# DAC.net
KiCad netlist of a schematic drawn in Altium Designer
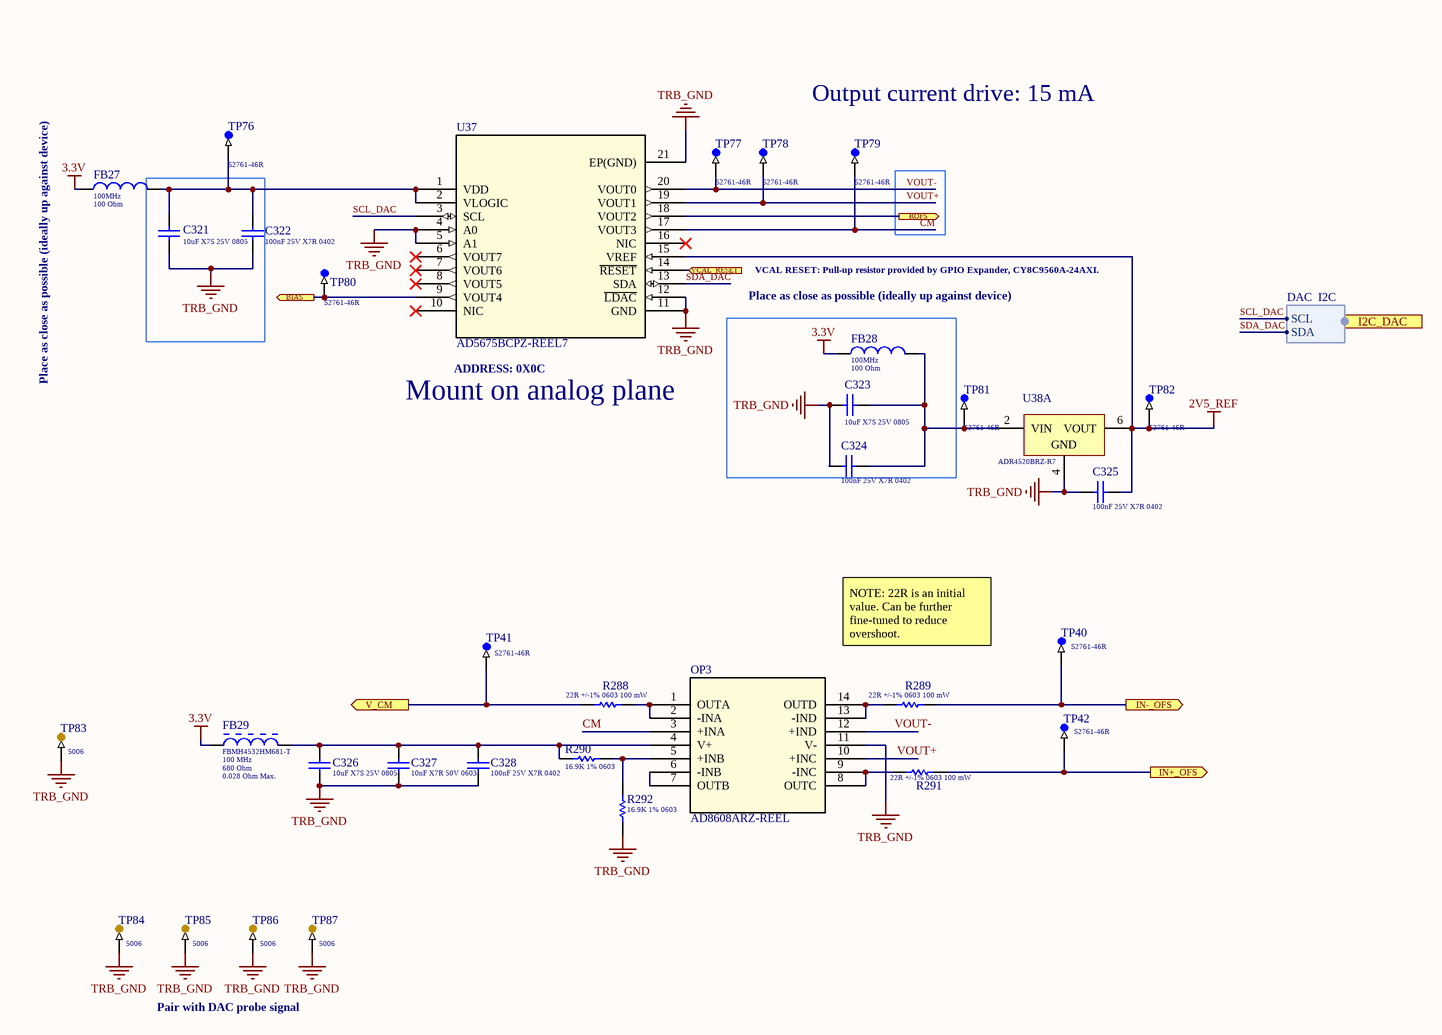
[diagram p0: DAC.SchDoc]

(export (version "E")
  (design (tool "Eeschema 10.0.6"))
  (components
    (comp (ref "C321")
      (value "Cap_Murata_ GRM21BC71E106ME11L_10uF")
      (footprint "Cap_Murata_ GRM21BC71E106ME11L_10uF")
      (description "CAP CER 10uF 25V X7R 0805")
      (fields (field (name "CAPACITANCE") "10uF X7S 25V 0805"))
      (libsource (lib "Cap_Murata_ GRM21BC71E106ME11L_10uF") (part "Cap_Murata_ GRM21BC71E106ME11L_10uF"))
    )
    (comp (ref "C322")
      (value "Cap_Taiyo_Yuden_TMK105B7104KV-FR_100nF")
      (footprint "Cap_Taiyo_Yuden_TMK105B7104KV-FR_100nF")
      (description "CAP CER 100nF 25V X7R 0402")
      (fields (field (name "CAPACITANCE") "100nF 25V X7R 0402"))
      (libsource (lib "Cap_Taiyo_Yuden_TMK105B7104KV-FR_100nF") (part "Cap_Taiyo_Yuden_TMK105B7104KV-FR_100nF"))
    )
    (comp (ref "C323")
      (value "Cap_Murata_ GRM21BC71E106ME11L_10uF")
      (footprint "Cap_Murata_ GRM21BC71E106ME11L_10uF")
      (description "CAP CER 10uF 25V X7R 0805")
      (fields (field (name "CAPACITANCE") "10uF X7S 25V 0805"))
      (libsource (lib "Cap_Murata_ GRM21BC71E106ME11L_10uF") (part "Cap_Murata_ GRM21BC71E106ME11L_10uF"))
    )
    (comp (ref "C324")
      (value "Cap_Taiyo_Yuden_TMK105B7104KV-FR_100nF")
      (footprint "Cap_Taiyo_Yuden_TMK105B7104KV-FR_100nF")
      (description "CAP CER 100nF 25V X7R 0402")
      (fields (field (name "CAPACITANCE") "100nF 25V X7R 0402"))
      (libsource (lib "Cap_Taiyo_Yuden_TMK105B7104KV-FR_100nF") (part "Cap_Taiyo_Yuden_TMK105B7104KV-FR_100nF"))
    )
    (comp (ref "C325")
      (value "Cap_Taiyo_Yuden_TMK105B7104KV-FR_100nF")
      (footprint "Cap_Taiyo_Yuden_TMK105B7104KV-FR_100nF")
      (description "CAP CER 100nF 25V X7R 0402")
      (fields (field (name "CAPACITANCE") "100nF 25V X7R 0402"))
      (libsource (lib "Cap_Taiyo_Yuden_TMK105B7104KV-FR_100nF") (part "Cap_Taiyo_Yuden_TMK105B7104KV-FR_100nF"))
    )
    (comp (ref "C326")
      (value "Cap_Murata_ GRM21BC71E106ME11L_10uF")
      (footprint "Cap_Murata_ GRM21BC71E106ME11L_10uF")
      (description "CAP CER 10uF 25V X7R 0805")
      (fields (field (name "CAPACITANCE") "10uF X7S 25V 0805"))
      (libsource (lib "Cap_Murata_ GRM21BC71E106ME11L_10uF") (part "Cap_Murata_ GRM21BC71E106ME11L_10uF"))
    )
    (comp (ref "C327")
      (value "Cap_Kemet_C0603C103J5RACTU_eec")
      (footprint "Kemet_C0603_0")
      (description "CAP CER 10nF 50V X7R 0603")
      (fields
        (field (name "PART NUMBER") "C0603C103J5RACTU")
        (field (name "MANUFACTURER") "Kemet")
        (field (name "CAPACITANCE") "10nF X7R 50V 0603")
      )
      (libsource (lib "Cap_Kemet_C0603C103J5RACTU_10nF") (part "Cap_Kemet_C0603C103J5RACTU_eec"))
    )
    (comp (ref "C328")
      (value "Cap_Taiyo_Yuden_TMK105B7104KV-FR_100nF")
      (footprint "Cap_Taiyo_Yuden_TMK105B7104KV-FR_100nF")
      (description "CAP CER 100nF 25V X7R 0402")
      (fields (field (name "CAPACITANCE") "100nF 25V X7R 0402"))
      (libsource (lib "Cap_Taiyo_Yuden_TMK105B7104KV-FR_100nF") (part "Cap_Taiyo_Yuden_TMK105B7104KV-FR_100nF"))
    )
    (comp (ref "FB27")
      (value "742792731")
      (footprint "FB_Wurth_Electronics_742792731_100Ohms")
      (description "FB SMD 100 OHM 25% 1.2A 0402")
      (fields (field (name "MEASURING FREQUENCY") "100MHz") (field (name "IMPEDANCE") "100 Ohm"))
      (libsource (lib "FB_Wurth_Electronics_742792731_100Ohms") (part "FB_Wurth_Electronics_742792731_100Ohms"))
    )
    (comp (ref "FB28")
      (value "742792731")
      (footprint "FB_Wurth_Electronics_742792731_100Ohms")
      (description "FB SMD 100 OHM 25% 1.2A 0402")
      (fields (field (name "MEASURING FREQUENCY") "100MHz") (field (name "IMPEDANCE") "100 Ohm"))
      (libsource (lib "FB_Wurth_Electronics_742792731_100Ohms") (part "FB_Wurth_Electronics_742792731_100Ohms"))
    )
    (comp (ref "FB29")
      (value "FBMH4532HM681-T")
      (footprint "TAYO-FBMH4532-2_V")
      (fields
        (field (name "PARTNUMBER") "FBMH4532HM681-T")
        (field (name "MANUFACTURER") "Taiyo Yuden")
        (field (name "MEASURING FREQUENCY") "100 MHz")
        (field (name "NOMINAL IMPEDANCE") "680 Ohm")
        (field (name "DC RESISTANCE") "0.028 Ohm Max.")
      )
      (libsource (lib "Taiyo_Yuden_FBMH4532HM681") (part "FBMH4532HM681-T"))
    )
    (comp (ref "OP3")
      (value "AD8608ARZ-REEL")
      (footprint "R_14_ADI-M")
      (description "IC OPAMP GP 4 CIRCUIT 14SOIC")
      (fields (field (name "COPYRIGHT") "Copyright (C) 2018 Accelerated Designs. All rights reserved"))
      (libsource (lib "IC_AnalogDevices_AD8608ARZ-REEL") (part "AD8608ARZ-REEL"))
    )
    (comp (ref "R288")
      (value "22R +/-1% 0603 100 mW")
      (footprint "RESC1609X50X30ML08T20")
      (description "Chip Resistor, 22 Ohm, +/- 1%, 100 mW, -55 to 155 degC, 0603 (1608 Metric)")
      (fields (field (name "TOLERANCE") "1%") (field (name "POWER") "100mW"))
      (libsource (lib "Sean Quinn") (part "RES-2"))
    )
    (comp (ref "R289")
      (value "22R +/-1% 0603 100 mW")
      (footprint "RESC1609X50X30ML08T20")
      (description "Chip Resistor, 22 Ohm, +/- 1%, 100 mW, -55 to 155 degC, 0603 (1608 Metric)")
      (fields (field (name "TOLERANCE") "1%") (field (name "POWER") "100mW"))
      (libsource (lib "Sean Quinn") (part "RES-2"))
    )
    (comp (ref "R290")
      (value "Res_Panasonic_ERJ-3EKF1692V_16.9kOhm")
      (footprint "Res_Panasonic_ERJ-3EKF1692V_16.9kOhm")
      (description "RES SMD 16.9k OHM 5% 1/10W 0603")
      (fields (field (name "RESISTANCE") "16.9K 1% 0603"))
      (libsource (lib "Res_Panasonic_ERJ-3EKF1692V_16.9kOhm") (part "Res_Panasonic_ERJ-3EKF1692V_16.9kOhm"))
    )
    (comp (ref "R291")
      (value "22R +/-1% 0603 100 mW")
      (footprint "RESC1609X50X30ML08T20")
      (description "Chip Resistor, 22 Ohm, +/- 1%, 100 mW, -55 to 155 degC, 0603 (1608 Metric)")
      (fields (field (name "TOLERANCE") "1%") (field (name "POWER") "100mW"))
      (libsource (lib "Sean Quinn") (part "RES-2"))
    )
    (comp (ref "R292")
      (value "Res_Panasonic_ERJ-3EKF1692V_16.9kOhm")
      (footprint "Res_Panasonic_ERJ-3EKF1692V_16.9kOhm")
      (description "RES SMD 16.9k OHM 5% 1/10W 0603")
      (fields (field (name "RESISTANCE") "16.9K 1% 0603"))
      (libsource (lib "Res_Panasonic_ERJ-3EKF1692V_16.9kOhm") (part "Res_Panasonic_ERJ-3EKF1692V_16.9kOhm"))
    )
    (comp (ref "TP40")
      (value "TP_Harwin_S2761_46R")
      (footprint "TP_Harwin_S2761_46R")
      (description "Circuit Board Hardware - PCB SMT Mini Test Terminal, Reel")
      (fields (field (name "SERIES") "S2761-46R"))
      (libsource (lib "TP_Harwin_S2761_46R") (part "TP_Harwin_S2761_46R"))
    )
    (comp (ref "TP41")
      (value "TP_Harwin_S2761_46R")
      (footprint "TP_Harwin_S2761_46R")
      (description "Circuit Board Hardware - PCB SMT Mini Test Terminal, Reel")
      (fields (field (name "SERIES") "S2761-46R"))
      (libsource (lib "TP_Harwin_S2761_46R") (part "TP_Harwin_S2761_46R"))
    )
    (comp (ref "TP42")
      (value "TP_Harwin_S2761_46R")
      (footprint "TP_Harwin_S2761_46R")
      (description "Circuit Board Hardware - PCB SMT Mini Test Terminal, Reel")
      (fields (field (name "SERIES") "S2761-46R"))
      (libsource (lib "TP_Harwin_S2761_46R") (part "TP_Harwin_S2761_46R"))
    )
    (comp (ref "TP76")
      (value "TP_Harwin_S2761_46R")
      (footprint "TP_Harwin_S2761_46R")
      (description "Circuit Board Hardware - PCB SMT Mini Test Terminal, Reel")
      (fields (field (name "SERIES") "S2761-46R"))
      (libsource (lib "TP_Harwin_S2761_46R") (part "TP_Harwin_S2761_46R"))
    )
    (comp (ref "TP77")
      (value "TP_Harwin_S2761_46R")
      (footprint "TP_Harwin_S2761_46R")
      (description "Circuit Board Hardware - PCB SMT Mini Test Terminal, Reel")
      (fields (field (name "SERIES") "S2761-46R"))
      (libsource (lib "TP_Harwin_S2761_46R") (part "TP_Harwin_S2761_46R"))
    )
    (comp (ref "TP78")
      (value "TP_Harwin_S2761_46R")
      (footprint "TP_Harwin_S2761_46R")
      (description "Circuit Board Hardware - PCB SMT Mini Test Terminal, Reel")
      (fields (field (name "SERIES") "S2761-46R"))
      (libsource (lib "TP_Harwin_S2761_46R") (part "TP_Harwin_S2761_46R"))
    )
    (comp (ref "TP79")
      (value "TP_Harwin_S2761_46R")
      (footprint "TP_Harwin_S2761_46R")
      (description "Circuit Board Hardware - PCB SMT Mini Test Terminal, Reel")
      (fields (field (name "SERIES") "S2761-46R"))
      (libsource (lib "TP_Harwin_S2761_46R") (part "TP_Harwin_S2761_46R"))
    )
    (comp (ref "TP80")
      (value "TP_Harwin_S2761_46R")
      (footprint "TP_Harwin_S2761_46R")
      (description "Circuit Board Hardware - PCB SMT Mini Test Terminal, Reel")
      (fields (field (name "SERIES") "S2761-46R"))
      (libsource (lib "TP_Harwin_S2761_46R") (part "TP_Harwin_S2761_46R"))
    )
    (comp (ref "TP81")
      (value "TP_Harwin_S2761_46R")
      (footprint "TP_Harwin_S2761_46R")
      (description "Circuit Board Hardware - PCB SMT Mini Test Terminal, Reel")
      (fields (field (name "SERIES") "S2761-46R"))
      (libsource (lib "TP_Harwin_S2761_46R") (part "TP_Harwin_S2761_46R"))
    )
    (comp (ref "TP82")
      (value "TP_Harwin_S2761_46R")
      (footprint "TP_Harwin_S2761_46R")
      (description "Circuit Board Hardware - PCB SMT Mini Test Terminal, Reel")
      (fields (field (name "SERIES") "S2761-46R"))
      (libsource (lib "TP_Harwin_S2761_46R") (part "TP_Harwin_S2761_46R"))
    )
    (comp (ref "TP83")
      (value "TP_Keystone_Electronics_5006")
      (footprint "TP_Keystone_Electronics_5006")
      (description "Circuit Board Hardware - PCB TEST POINT BLK .063")
      (fields (field (name "SERIES") "5006"))
      (libsource (lib "TP_Keystone_Electronics_5006") (part "TP_Keystone_Electronics_5006"))
    )
    (comp (ref "TP84")
      (value "TP_Keystone_Electronics_5006")
      (footprint "TP_Keystone_Electronics_5006")
      (description "Circuit Board Hardware - PCB TEST POINT BLK .063")
      (fields (field (name "SERIES") "5006"))
      (libsource (lib "TP_Keystone_Electronics_5006") (part "TP_Keystone_Electronics_5006"))
    )
    (comp (ref "TP85")
      (value "TP_Keystone_Electronics_5006")
      (footprint "TP_Keystone_Electronics_5006")
      (description "Circuit Board Hardware - PCB TEST POINT BLK .063")
      (fields (field (name "SERIES") "5006"))
      (libsource (lib "TP_Keystone_Electronics_5006") (part "TP_Keystone_Electronics_5006"))
    )
    (comp (ref "TP86")
      (value "TP_Keystone_Electronics_5006")
      (footprint "TP_Keystone_Electronics_5006")
      (description "Circuit Board Hardware - PCB TEST POINT BLK .063")
      (fields (field (name "SERIES") "5006"))
      (libsource (lib "TP_Keystone_Electronics_5006") (part "TP_Keystone_Electronics_5006"))
    )
    (comp (ref "TP87")
      (value "TP_Keystone_Electronics_5006")
      (footprint "TP_Keystone_Electronics_5006")
      (description "Circuit Board Hardware - PCB TEST POINT BLK .063")
      (fields (field (name "SERIES") "5006"))
      (libsource (lib "TP_Keystone_Electronics_5006") (part "TP_Keystone_Electronics_5006"))
    )
    (comp (ref "U37")
      (value "AD5675")
      (footprint "CP_20_8")
      (description "Digital to Analog Converters - DAC 16-bit octal I2C nanoDAC")
      (fields
        (field (name "MANUFACTURER_PART_NUMBER") "AD5675BCPZ-REEL7")
        (field (name "SERIES") "AD5675BCPZ-REEL7")
      )
      (libsource (lib "AD5675BCPZ-REEL7") (part "AD5675BCPZ-REEL7"))
    )
    (comp (ref "U38")
      (value "ADR4520BRZ-R7")
      (footprint "ADI-R-8_M")
      (fields (field (name "MANUFACTURER") "Analog Devices"))
      (libsource (lib "Altium Content Vault") (part "ADI-ADR45xx-R-8"))
    )
  )
  (nets
    (net (code "3") (name "/BIAS") (class "Default")
      (node (ref "TP80") (pin "1") (pinfunction "1_1") (pintype "input"))
      (node (ref "U37") (pin "9") (pinfunction "VOUT4_9") (pintype "output"))
    )
    (net (code "4") (name "/CM") (class "Default")
      (node (ref "OP3") (pin "3") (pinfunction "+INA_3") (pintype "passive"))
      (node (ref "TP79") (pin "1") (pinfunction "1_1") (pintype "input"))
      (node (ref "U37") (pin "17") (pinfunction "VOUT3_17") (pintype "output"))
    )
    (net (code "5") (name "/IN+_OFS") (class "Default")
      (node (ref "R291") (pin "2") (pinfunction "2_2") (pintype "passive"))
      (node (ref "TP42") (pin "1") (pinfunction "1_1") (pintype "input"))
    )
    (net (code "6") (name "/IN-_OFS") (class "Default")
      (node (ref "R289") (pin "2") (pinfunction "2_2") (pintype "passive"))
      (node (ref "TP40") (pin "1") (pinfunction "1_1") (pintype "input"))
    )
    (net (code "7") (name "/ROFS") (class "Default")
      (node (ref "U37") (pin "18") (pinfunction "VOUT2_18") (pintype "output"))
    )
    (net (code "8") (name "/SCL_DAC") (class "Default")
      (node (ref "U37") (pin "3") (pinfunction "SCL_3") (pintype "bidirectional"))
    )
    (net (code "9") (name "/SDA_DAC") (class "Default")
      (node (ref "U37") (pin "13") (pinfunction "SDA_13") (pintype "bidirectional"))
    )
    (net (code "10") (name "/VCAL_RESET") (class "Default")
      (node (ref "U37") (pin "14") (pinfunction "~{RESET}_14") (pintype "input"))
    )
    (net (code "11") (name "/VOUT+") (class "Default")
      (node (ref "OP3") (pin "10") (pinfunction "+INC_10") (pintype "passive"))
      (node (ref "TP78") (pin "1") (pinfunction "1_1") (pintype "input"))
      (node (ref "U37") (pin "19") (pinfunction "VOUT1_19") (pintype "output"))
    )
    (net (code "12") (name "/VOUT-") (class "Default")
      (node (ref "OP3") (pin "12") (pinfunction "+IND_12") (pintype "passive"))
      (node (ref "TP77") (pin "1") (pinfunction "1_1") (pintype "input"))
      (node (ref "U37") (pin "20") (pinfunction "VOUT0_20") (pintype "output"))
    )
    (net (code "13") (name "/V_CM") (class "Default")
      (node (ref "R288") (pin "1") (pinfunction "1_1") (pintype "passive"))
      (node (ref "TP41") (pin "1") (pinfunction "1_1") (pintype "input"))
    )
    (net (code "15") (name "2V5_REF") (class "Default")
      (node (ref "C325") (pin "2") (pinfunction "2_2") (pintype "passive"))
      (node (ref "TP82") (pin "1") (pinfunction "1_1") (pintype "input"))
      (node (ref "U37") (pin "15") (pinfunction "VREF_15") (pintype "input"))
      (node (ref "U38") (pin "6") (pinfunction "VOUT_6") (pintype "power_in"))
    )
    (net (code "16") (name "3.3V") (class "Default")
      (node (ref "FB27") (pin "1") (pinfunction "1_1") (pintype "passive"))
      (node (ref "FB28") (pin "1") (pinfunction "1_1") (pintype "passive"))
      (node (ref "FB29") (pin "1") (pinfunction "1_1") (pintype "passive"))
    )
    (net (code "17") (name "Net-(OP3-+INB)") (class "Default")
      (node (ref "OP3") (pin "5") (pinfunction "+INB_5") (pintype "passive"))
      (node (ref "R290") (pin "1") (pinfunction "1_1") (pintype "passive"))
      (node (ref "R292") (pin "1") (pinfunction "1_1") (pintype "passive"))
    )
    (net (code "18") (name "Net-(OP3--INA)") (class "Default")
      (node (ref "OP3") (pin "1") (pinfunction "OUTA_1") (pintype "passive"))
      (node (ref "OP3") (pin "2") (pinfunction "-INA_2") (pintype "passive"))
      (node (ref "R288") (pin "2") (pinfunction "2_2") (pintype "passive"))
    )
    (net (code "19") (name "Net-(OP3--INB)") (class "Default")
      (node (ref "OP3") (pin "6") (pinfunction "-INB_6") (pintype "passive"))
      (node (ref "OP3") (pin "7") (pinfunction "OUTB_7") (pintype "passive"))
    )
    (net (code "20") (name "Net-(OP3--INC)") (class "Default")
      (node (ref "OP3") (pin "8") (pinfunction "OUTC_8") (pintype "passive"))
      (node (ref "OP3") (pin "9") (pinfunction "-INC_9") (pintype "passive"))
      (node (ref "R291") (pin "1") (pinfunction "1_1") (pintype "passive"))
    )
    (net (code "21") (name "Net-(OP3--IND)") (class "Default")
      (node (ref "OP3") (pin "13") (pinfunction "-IND_13") (pintype "passive"))
      (node (ref "OP3") (pin "14") (pinfunction "OUTD_14") (pintype "passive"))
      (node (ref "R289") (pin "1") (pinfunction "1_1") (pintype "passive"))
    )
    (net (code "22") (name "Net-(OP3-V+)") (class "Default")
      (node (ref "C326") (pin "1") (pinfunction "1_1") (pintype "passive"))
      (node (ref "C327") (pin "1") (pinfunction "1_1") (pintype "passive"))
      (node (ref "C328") (pin "2") (pinfunction "2_2") (pintype "passive"))
      (node (ref "FB29") (pin "2") (pinfunction "2_2") (pintype "passive"))
      (node (ref "OP3") (pin "4") (pinfunction "V+_4") (pintype "power_in"))
      (node (ref "R290") (pin "2") (pinfunction "2_2") (pintype "passive"))
    )
    (net (code "23") (name "Net-(U37-VDD)") (class "Default")
      (node (ref "C321") (pin "1") (pinfunction "1_1") (pintype "passive"))
      (node (ref "C322") (pin "2") (pinfunction "2_2") (pintype "passive"))
      (node (ref "FB27") (pin "2") (pinfunction "2_2") (pintype "passive"))
      (node (ref "TP76") (pin "1") (pinfunction "1_1") (pintype "input"))
      (node (ref "U37") (pin "1") (pinfunction "VDD_1") (pintype "power_in"))
      (node (ref "U37") (pin "2") (pinfunction "VLOGIC_2") (pintype "power_in"))
    )
    (net (code "24") (name "Net-(U38A-VIN)") (class "Default")
      (node (ref "C323") (pin "1") (pinfunction "1_1") (pintype "passive"))
      (node (ref "C324") (pin "2") (pinfunction "2_2") (pintype "passive"))
      (node (ref "FB28") (pin "2") (pinfunction "2_2") (pintype "passive"))
      (node (ref "TP81") (pin "1") (pinfunction "1_1") (pintype "input"))
      (node (ref "U38") (pin "2") (pinfunction "VIN_2") (pintype "power_in"))
    )
    (net (code "25") (name "TRB_GND") (class "Default")
      (node (ref "C321") (pin "2") (pinfunction "2_2") (pintype "passive"))
      (node (ref "C322") (pin "1") (pinfunction "1_1") (pintype "passive"))
      (node (ref "C323") (pin "2") (pinfunction "2_2") (pintype "passive"))
      (node (ref "C324") (pin "1") (pinfunction "1_1") (pintype "passive"))
      (node (ref "C325") (pin "1") (pinfunction "1_1") (pintype "passive"))
      (node (ref "C326") (pin "2") (pinfunction "2_2") (pintype "passive"))
      (node (ref "C327") (pin "2") (pinfunction "2_2") (pintype "passive"))
      (node (ref "C328") (pin "1") (pinfunction "1_1") (pintype "passive"))
      (node (ref "OP3") (pin "11") (pinfunction "V-_11") (pintype "power_in"))
      (node (ref "R292") (pin "2") (pinfunction "2_2") (pintype "passive"))
      (node (ref "TP83") (pin "1") (pinfunction "1_1") (pintype "input"))
      (node (ref "TP84") (pin "1") (pinfunction "1_1") (pintype "input"))
      (node (ref "TP85") (pin "1") (pinfunction "1_1") (pintype "input"))
      (node (ref "TP86") (pin "1") (pinfunction "1_1") (pintype "input"))
      (node (ref "TP87") (pin "1") (pinfunction "1_1") (pintype "input"))
      (node (ref "U37") (pin "11") (pinfunction "GND_11") (pintype "passive"))
      (node (ref "U37") (pin "12") (pinfunction "~{LDAC}_12") (pintype "input"))
      (node (ref "U37") (pin "21") (pinfunction "EP(GND)_21") (pintype "passive"))
      (node (ref "U37") (pin "4") (pinfunction "A0_4") (pintype "input"))
      (node (ref "U37") (pin "5") (pinfunction "A1_5") (pintype "input"))
      (node (ref "U38") (pin "4") (pinfunction "GND_4") (pintype "power_in"))
    )
    (net (code "26") (name "unconnected-(U37-NIC-Pad10)") (class "Default")
      (node (ref "U37") (pin "10") (pinfunction "NIC_10") (pintype "passive+no_connect"))
    )
    (net (code "27") (name "unconnected-(U37-NIC-Pad16)") (class "Default")
      (node (ref "U37") (pin "16") (pinfunction "NIC_16") (pintype "passive+no_connect"))
    )
    (net (code "28") (name "unconnected-(U37-VOUT5-Pad8)") (class "Default")
      (node (ref "U37") (pin "8") (pinfunction "VOUT5_8") (pintype "output+no_connect"))
    )
    (net (code "29") (name "unconnected-(U37-VOUT6-Pad7)") (class "Default")
      (node (ref "U37") (pin "7") (pinfunction "VOUT6_7") (pintype "output+no_connect"))
    )
    (net (code "30") (name "unconnected-(U37-VOUT7-Pad6)") (class "Default")
      (node (ref "U37") (pin "6") (pinfunction "VOUT7_6") (pintype "output+no_connect"))
    )
  )
)
